# R2Cloud.net
KiCad netlist of a schematic drawn in Altium Designer
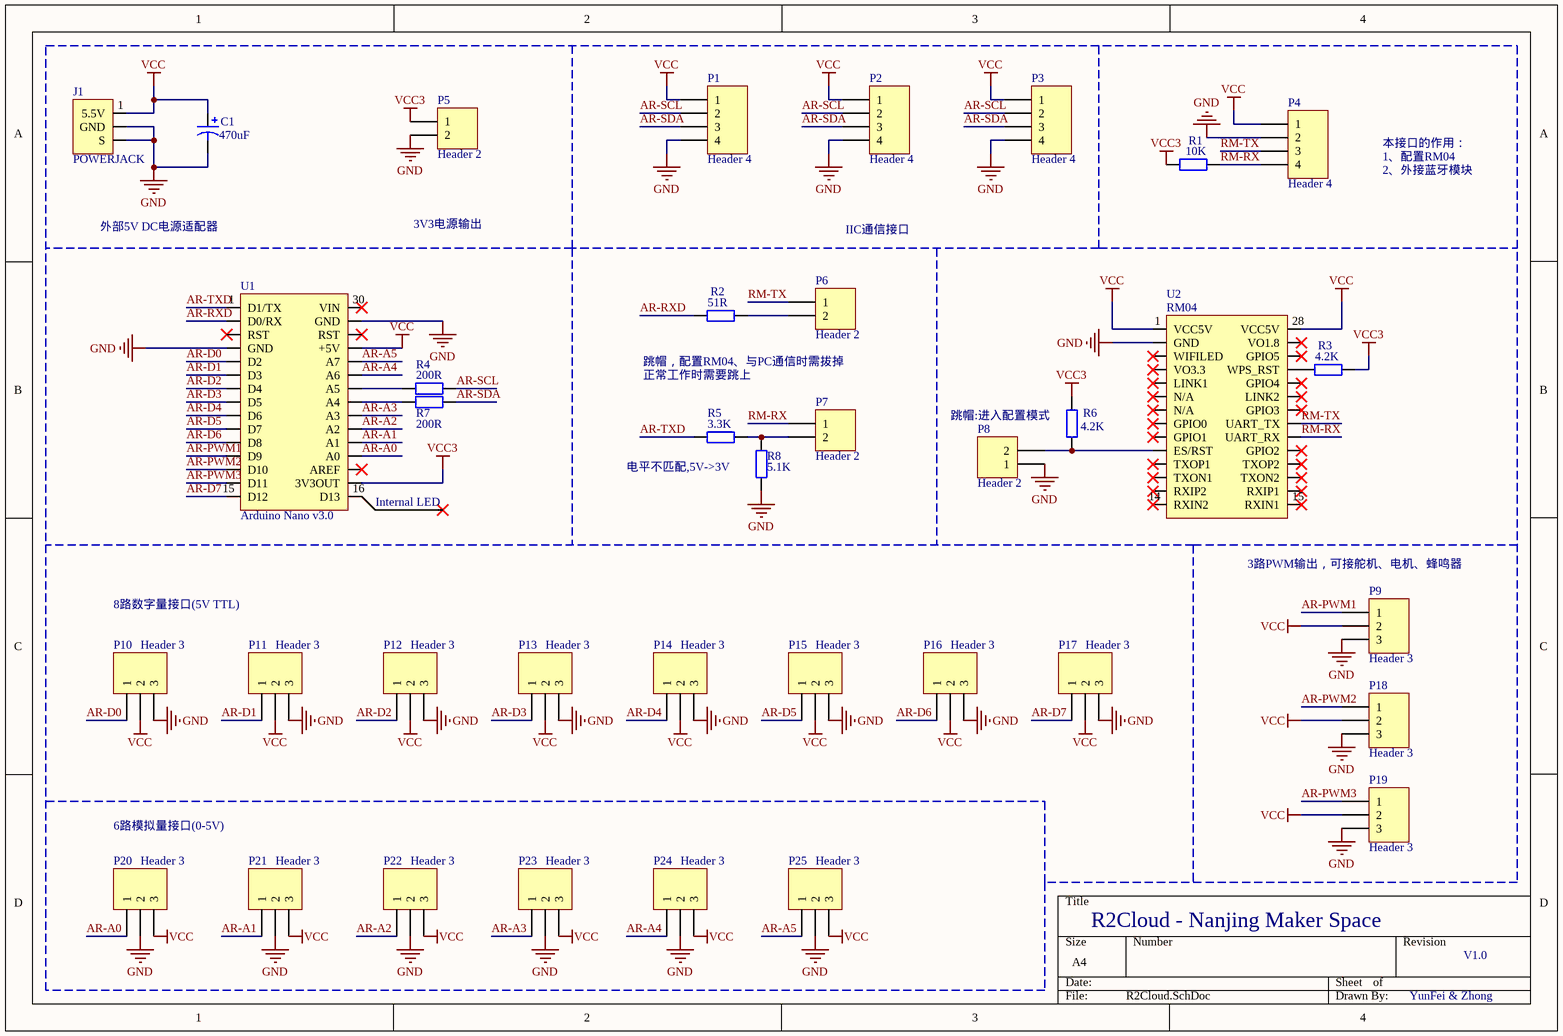
[diagram p0: R2Cloud.SchDoc]

(export (version "E")
  (design (tool "Eeschema 10.0.6"))
  (components
    (comp (ref "C1")
      (value "470uF")
      (footprint "C3.81/7.62")
      (description "Polarized Capacitor (Surface Mount)")
      (fields (field (name "Comment") "Cap Pol3") (field (name "PUBLISHER") "Altium Limited"))
      (libsource (lib "Miscellaneous Devices") (part "Cap Pol3"))
    )
    (comp (ref "J1") (value "POWERJACK") (footprint "POWERJACK") (libsource (lib "YAOJI") (part "POWERJACK")))
    (comp (ref "P1")
      (value "Header 4")
      (footprint "CON4-IIC")
      (description "Header, 4-Pin")
      (fields (field (name "PUBLISHER") "Altium Limited"))
      (libsource (lib "Miscellaneous Connectors") (part "Header 4"))
    )
    (comp (ref "P2")
      (value "Header 4")
      (footprint "CON4-IIC")
      (description "Header, 4-Pin")
      (fields (field (name "PUBLISHER") "Altium Limited"))
      (libsource (lib "Miscellaneous Connectors") (part "Header 4"))
    )
    (comp (ref "P3")
      (value "Header 4")
      (footprint "CON4-IIC")
      (description "Header, 4-Pin")
      (fields (field (name "PUBLISHER") "Altium Limited"))
      (libsource (lib "Miscellaneous Connectors") (part "Header 4"))
    )
    (comp (ref "P4")
      (value "Header 4")
      (footprint "CON4-EX")
      (description "Header, 4-Pin")
      (fields (field (name "PUBLISHER") "Altium Limited"))
      (libsource (lib "Miscellaneous Connectors") (part "Header 4"))
    )
    (comp (ref "P5")
      (value "Header 2")
      (footprint "CON2-V3.3")
      (description "Header, 2-Pin")
      (fields (field (name "PUBLISHER") "Altium Limited"))
      (libsource (lib "") (part "Header 2_1"))
    )
    (comp (ref "P6")
      (value "Header 2")
      (footprint "CON2-JUMPER")
      (description "Header, 2-Pin")
      (fields (field (name "PUBLISHER") "Altium Limited"))
      (libsource (lib "") (part "Header 2_1"))
    )
    (comp (ref "P7")
      (value "Header 2")
      (footprint "CON2-JUMPER")
      (description "Header, 2-Pin")
      (fields (field (name "PUBLISHER") "Altium Limited"))
      (libsource (lib "") (part "Header 2_1"))
    )
    (comp (ref "P8")
      (value "Header 2")
      (footprint "CON2-JUMPER")
      (description "Header, 2-Pin")
      (fields (field (name "PUBLISHER") "Altium Limited"))
      (libsource (lib "Miscellaneous Connectors") (part "Header 2"))
    )
    (comp (ref "P9")
      (value "Header 3")
      (footprint "CON3-PWM")
      (description "Header, 3-Pin")
      (fields (field (name "PUBLISHER") "Altium Limited"))
      (libsource (lib "") (part "Header 3_1"))
    )
    (comp (ref "P10")
      (value "Header 3")
      (footprint "CON3-D")
      (description "Header, 3-Pin")
      (fields (field (name "PUBLISHER") "Altium Limited"))
      (libsource (lib "Miscellaneous Connectors") (part "Header 3"))
    )
    (comp (ref "P11")
      (value "Header 3")
      (footprint "CON3-D")
      (description "Header, 3-Pin")
      (fields (field (name "PUBLISHER") "Altium Limited"))
      (libsource (lib "Miscellaneous Connectors") (part "Header 3"))
    )
    (comp (ref "P12")
      (value "Header 3")
      (footprint "CON3-D")
      (description "Header, 3-Pin")
      (fields (field (name "PUBLISHER") "Altium Limited"))
      (libsource (lib "Miscellaneous Connectors") (part "Header 3"))
    )
    (comp (ref "P13")
      (value "Header 3")
      (footprint "CON3-D")
      (description "Header, 3-Pin")
      (fields (field (name "PUBLISHER") "Altium Limited"))
      (libsource (lib "Miscellaneous Connectors") (part "Header 3"))
    )
    (comp (ref "P14")
      (value "Header 3")
      (footprint "CON3-D")
      (description "Header, 3-Pin")
      (fields (field (name "PUBLISHER") "Altium Limited"))
      (libsource (lib "Miscellaneous Connectors") (part "Header 3"))
    )
    (comp (ref "P15")
      (value "Header 3")
      (footprint "CON3-D")
      (description "Header, 3-Pin")
      (fields (field (name "PUBLISHER") "Altium Limited"))
      (libsource (lib "Miscellaneous Connectors") (part "Header 3"))
    )
    (comp (ref "P16")
      (value "Header 3")
      (footprint "CON3-D")
      (description "Header, 3-Pin")
      (fields (field (name "PUBLISHER") "Altium Limited"))
      (libsource (lib "Miscellaneous Connectors") (part "Header 3"))
    )
    (comp (ref "P17")
      (value "Header 3")
      (footprint "CON3-D")
      (description "Header, 3-Pin")
      (fields (field (name "PUBLISHER") "Altium Limited"))
      (libsource (lib "Miscellaneous Connectors") (part "Header 3"))
    )
    (comp (ref "P18")
      (value "Header 3")
      (footprint "CON3-PWM")
      (description "Header, 3-Pin")
      (fields (field (name "PUBLISHER") "Altium Limited"))
      (libsource (lib "") (part "Header 3_1"))
    )
    (comp (ref "P19")
      (value "Header 3")
      (footprint "CON3-PWM")
      (description "Header, 3-Pin")
      (fields (field (name "PUBLISHER") "Altium Limited"))
      (libsource (lib "") (part "Header 3_1"))
    )
    (comp (ref "P20")
      (value "Header 3")
      (footprint "CON3-A")
      (description "Header, 3-Pin")
      (fields (field (name "PUBLISHER") "Altium Limited"))
      (libsource (lib "Miscellaneous Connectors") (part "Header 3"))
    )
    (comp (ref "P21")
      (value "Header 3")
      (footprint "CON3-A")
      (description "Header, 3-Pin")
      (fields (field (name "PUBLISHER") "Altium Limited"))
      (libsource (lib "Miscellaneous Connectors") (part "Header 3"))
    )
    (comp (ref "P22")
      (value "Header 3")
      (footprint "CON3-A")
      (description "Header, 3-Pin")
      (fields (field (name "PUBLISHER") "Altium Limited"))
      (libsource (lib "Miscellaneous Connectors") (part "Header 3"))
    )
    (comp (ref "P23")
      (value "Header 3")
      (footprint "CON3-A")
      (description "Header, 3-Pin")
      (fields (field (name "PUBLISHER") "Altium Limited"))
      (libsource (lib "Miscellaneous Connectors") (part "Header 3"))
    )
    (comp (ref "P24")
      (value "Header 3")
      (footprint "CON3-A")
      (description "Header, 3-Pin")
      (fields (field (name "PUBLISHER") "Altium Limited"))
      (libsource (lib "Miscellaneous Connectors") (part "Header 3"))
    )
    (comp (ref "P25")
      (value "Header 3")
      (footprint "CON3-A")
      (description "Header, 3-Pin")
      (fields (field (name "PUBLISHER") "Altium Limited"))
      (libsource (lib "Miscellaneous Connectors") (part "Header 3"))
    )
    (comp (ref "R1")
      (value "10K")
      (footprint "0603")
      (description "Resistor")
      (fields (field (name "Comment") "Res2") (field (name "PUBLISHER") "Altium Limited"))
      (libsource (lib "Miscellaneous Devices") (part "Res2"))
    )
    (comp (ref "R2")
      (value "51R")
      (footprint "0603")
      (description "Resistor")
      (fields (field (name "Comment") "Res2") (field (name "PUBLISHER") "Altium Limited"))
      (libsource (lib "Miscellaneous Devices") (part "Res2"))
    )
    (comp (ref "R3")
      (value "4.2K")
      (footprint "0603")
      (description "Resistor")
      (fields (field (name "Comment") "Res2") (field (name "PUBLISHER") "Altium Limited"))
      (libsource (lib "Miscellaneous Devices") (part "Res2"))
    )
    (comp (ref "R4")
      (value "200R")
      (footprint "0603")
      (description "Resistor")
      (fields (field (name "Comment") "Res2") (field (name "PUBLISHER") "Altium Limited"))
      (libsource (lib "Miscellaneous Devices") (part "Res2"))
    )
    (comp (ref "R5")
      (value "3.3K")
      (footprint "0603")
      (description "Resistor")
      (fields (field (name "Comment") "Res2") (field (name "PUBLISHER") "Altium Limited"))
      (libsource (lib "Miscellaneous Devices") (part "Res2"))
    )
    (comp (ref "R6")
      (value "4.2K")
      (footprint "0603")
      (description "Resistor")
      (fields (field (name "Comment") "Res2") (field (name "PUBLISHER") "Altium Limited"))
      (libsource (lib "") (part "Res2_1"))
    )
    (comp (ref "R7")
      (value "200R")
      (footprint "0603")
      (description "Resistor")
      (fields (field (name "Comment") "Res2") (field (name "PUBLISHER") "Altium Limited"))
      (libsource (lib "Miscellaneous Devices") (part "Res2"))
    )
    (comp (ref "R8")
      (value "5.1K")
      (footprint "0603")
      (description "Resistor")
      (fields (field (name "Comment") "Res2") (field (name "PUBLISHER") "Altium Limited"))
      (libsource (lib "") (part "Res2_2"))
    )
    (comp (ref "U1")
      (value "Arduino Nano v3.0")
      (footprint "Arduino Nano v3.0")
      (libsource (lib "YAOJI") (part "Arduino Nano v3.0"))
    )
    (comp (ref "U2") (value "RM04") (footprint "RM-04") (libsource (lib "YAOJI") (part "RM04")))
  )
  (nets
    (net (code "1") (name "/AR-A0") (class "Default")
      (node (ref "P20") (pin "1") (pinfunction "1_1") (pintype "passive"))
      (node (ref "U1") (pin "19") (pinfunction "A0_19") (pintype "passive"))
    )
    (net (code "2") (name "/AR-A1") (class "Default")
      (node (ref "P21") (pin "1") (pinfunction "1_1") (pintype "passive"))
      (node (ref "U1") (pin "20") (pinfunction "A1_20") (pintype "passive"))
    )
    (net (code "3") (name "/AR-A2") (class "Default")
      (node (ref "P22") (pin "1") (pinfunction "1_1") (pintype "passive"))
      (node (ref "U1") (pin "21") (pinfunction "A2_21") (pintype "passive"))
    )
    (net (code "4") (name "/AR-A3") (class "Default")
      (node (ref "P23") (pin "1") (pinfunction "1_1") (pintype "passive"))
      (node (ref "U1") (pin "22") (pinfunction "A3_22") (pintype "passive"))
    )
    (net (code "5") (name "/AR-A4") (class "Default")
      (node (ref "P24") (pin "1") (pinfunction "1_1") (pintype "passive"))
      (node (ref "U1") (pin "25") (pinfunction "A6_25") (pintype "passive"))
    )
    (net (code "6") (name "/AR-A5") (class "Default")
      (node (ref "P25") (pin "1") (pinfunction "1_1") (pintype "passive"))
      (node (ref "U1") (pin "26") (pinfunction "A7_26") (pintype "passive"))
    )
    (net (code "7") (name "/AR-D0") (class "Default")
      (node (ref "P10") (pin "1") (pinfunction "1_1") (pintype "passive"))
      (node (ref "U1") (pin "5") (pinfunction "D2_5") (pintype "passive"))
    )
    (net (code "8") (name "/AR-D1") (class "Default")
      (node (ref "P11") (pin "1") (pinfunction "1_1") (pintype "passive"))
      (node (ref "U1") (pin "6") (pinfunction "D3_6") (pintype "passive"))
    )
    (net (code "9") (name "/AR-D2") (class "Default")
      (node (ref "P12") (pin "1") (pinfunction "1_1") (pintype "passive"))
      (node (ref "U1") (pin "7") (pinfunction "D4_7") (pintype "passive"))
    )
    (net (code "10") (name "/AR-D3") (class "Default")
      (node (ref "P13") (pin "1") (pinfunction "1_1") (pintype "passive"))
      (node (ref "U1") (pin "8") (pinfunction "D5_8") (pintype "passive"))
    )
    (net (code "11") (name "/AR-D4") (class "Default")
      (node (ref "P14") (pin "1") (pinfunction "1_1") (pintype "passive"))
      (node (ref "U1") (pin "9") (pinfunction "D6_9") (pintype "passive"))
    )
    (net (code "12") (name "/AR-D5") (class "Default")
      (node (ref "P15") (pin "1") (pinfunction "1_1") (pintype "passive"))
      (node (ref "U1") (pin "10") (pinfunction "D7_10") (pintype "passive"))
    )
    (net (code "13") (name "/AR-D6") (class "Default")
      (node (ref "P16") (pin "1") (pinfunction "1_1") (pintype "passive"))
      (node (ref "U1") (pin "11") (pinfunction "D8_11") (pintype "passive"))
    )
    (net (code "14") (name "/AR-D7") (class "Default")
      (node (ref "P17") (pin "1") (pinfunction "1_1") (pintype "passive"))
      (node (ref "U1") (pin "15") (pinfunction "D12_15") (pintype "passive"))
    )
    (net (code "15") (name "/AR-PWM1") (class "Default")
      (node (ref "P9") (pin "1") (pinfunction "1_1") (pintype "passive"))
      (node (ref "U1") (pin "12") (pinfunction "D9_12") (pintype "passive"))
    )
    (net (code "16") (name "/AR-PWM2") (class "Default")
      (node (ref "P18") (pin "1") (pinfunction "1_1") (pintype "passive"))
      (node (ref "U1") (pin "13") (pinfunction "D10_13") (pintype "passive"))
    )
    (net (code "17") (name "/AR-PWM3") (class "Default")
      (node (ref "P19") (pin "1") (pinfunction "1_1") (pintype "passive"))
      (node (ref "U1") (pin "14") (pinfunction "D11_14") (pintype "passive"))
    )
    (net (code "18") (name "/AR-RXD") (class "Default")
      (node (ref "R2") (pin "2") (pinfunction "2_2") (pintype "passive"))
      (node (ref "U1") (pin "2") (pinfunction "D0/RX_2") (pintype "passive"))
    )
    (net (code "19") (name "/AR-SCL") (class "Default")
      (node (ref "P1") (pin "2") (pinfunction "2_2") (pintype "passive"))
      (node (ref "P2") (pin "2") (pinfunction "2_2") (pintype "passive"))
      (node (ref "P3") (pin "2") (pinfunction "2_2") (pintype "passive"))
      (node (ref "R4") (pin "1") (pinfunction "1_1") (pintype "passive"))
    )
    (net (code "20") (name "/AR-SDA") (class "Default")
      (node (ref "P1") (pin "3") (pinfunction "3_3") (pintype "passive"))
      (node (ref "P2") (pin "3") (pinfunction "3_3") (pintype "passive"))
      (node (ref "P3") (pin "3") (pinfunction "3_3") (pintype "passive"))
      (node (ref "R7") (pin "1") (pinfunction "1_1") (pintype "passive"))
    )
    (net (code "21") (name "/AR-TXD") (class "Default")
      (node (ref "R5") (pin "2") (pinfunction "2_2") (pintype "passive"))
      (node (ref "U1") (pin "1") (pinfunction "D1/TX_1") (pintype "passive"))
    )
    (net (code "22") (name "/RM-RX") (class "Default")
      (node (ref "P4") (pin "4") (pinfunction "4_4") (pintype "passive"))
      (node (ref "P7") (pin "1") (pinfunction "1_1") (pintype "passive"))
      (node (ref "R1") (pin "1") (pinfunction "1_1") (pintype "passive"))
      (node (ref "U2") (pin "20") (pinfunction "UART_RX_20") (pintype "passive"))
    )
    (net (code "23") (name "/RM-TX") (class "Default")
      (node (ref "P4") (pin "3") (pinfunction "3_3") (pintype "passive"))
      (node (ref "P6") (pin "1") (pinfunction "1_1") (pintype "passive"))
      (node (ref "U2") (pin "21") (pinfunction "UART_TX_21") (pintype "passive"))
    )
    (net (code "24") (name "GND") (class "Default")
      (node (ref "C1") (pin "2") (pinfunction "2_2") (pintype "passive"))
      (node (ref "J1") (pin "2") (pinfunction "GND_2") (pintype "passive"))
      (node (ref "J1") (pin "3") (pinfunction "S_3") (pintype "passive"))
      (node (ref "P1") (pin "4") (pinfunction "4_4") (pintype "passive"))
      (node (ref "P10") (pin "3") (pinfunction "3_3") (pintype "passive"))
      (node (ref "P11") (pin "3") (pinfunction "3_3") (pintype "passive"))
      (node (ref "P12") (pin "3") (pinfunction "3_3") (pintype "passive"))
      (node (ref "P13") (pin "3") (pinfunction "3_3") (pintype "passive"))
      (node (ref "P14") (pin "3") (pinfunction "3_3") (pintype "passive"))
      (node (ref "P15") (pin "3") (pinfunction "3_3") (pintype "passive"))
      (node (ref "P16") (pin "3") (pinfunction "3_3") (pintype "passive"))
      (node (ref "P17") (pin "3") (pinfunction "3_3") (pintype "passive"))
      (node (ref "P18") (pin "3") (pinfunction "3_3") (pintype "passive"))
      (node (ref "P19") (pin "3") (pinfunction "3_3") (pintype "passive"))
      (node (ref "P2") (pin "4") (pinfunction "4_4") (pintype "passive"))
      (node (ref "P20") (pin "2") (pinfunction "2_2") (pintype "passive"))
      (node (ref "P21") (pin "2") (pinfunction "2_2") (pintype "passive"))
      (node (ref "P22") (pin "2") (pinfunction "2_2") (pintype "passive"))
      (node (ref "P23") (pin "2") (pinfunction "2_2") (pintype "passive"))
      (node (ref "P24") (pin "2") (pinfunction "2_2") (pintype "passive"))
      (node (ref "P25") (pin "2") (pinfunction "2_2") (pintype "passive"))
      (node (ref "P3") (pin "4") (pinfunction "4_4") (pintype "passive"))
      (node (ref "P4") (pin "2") (pinfunction "2_2") (pintype "passive"))
      (node (ref "P5") (pin "2") (pinfunction "2_2") (pintype "passive"))
      (node (ref "P8") (pin "1") (pinfunction "1_1") (pintype "passive"))
      (node (ref "P9") (pin "3") (pinfunction "3_3") (pintype "passive"))
      (node (ref "R8") (pin "2") (pinfunction "2_2") (pintype "passive"))
      (node (ref "U1") (pin "29") (pinfunction "GND_29") (pintype "passive"))
      (node (ref "U1") (pin "4") (pinfunction "GND_4") (pintype "passive"))
      (node (ref "U2") (pin "2") (pinfunction "GND_2") (pintype "passive"))
    )
    (net (code "25") (name "Net-(P6-Pad2)") (class "Default")
      (node (ref "P6") (pin "2") (pinfunction "2_2") (pintype "passive"))
      (node (ref "R2") (pin "1") (pinfunction "1_1") (pintype "passive"))
    )
    (net (code "26") (name "Net-(P7-Pad2)") (class "Default")
      (node (ref "P7") (pin "2") (pinfunction "2_2") (pintype "passive"))
      (node (ref "R5") (pin "1") (pinfunction "1_1") (pintype "passive"))
      (node (ref "R8") (pin "1") (pinfunction "1_1") (pintype "passive"))
    )
    (net (code "27") (name "Net-(U1-A4)") (class "Default")
      (node (ref "R7") (pin "2") (pinfunction "2_2") (pintype "passive"))
      (node (ref "U1") (pin "23") (pinfunction "A4_23") (pintype "passive"))
    )
    (net (code "28") (name "Net-(U1-A5)") (class "Default")
      (node (ref "R4") (pin "2") (pinfunction "2_2") (pintype "passive"))
      (node (ref "U1") (pin "24") (pinfunction "A5_24") (pintype "passive"))
    )
    (net (code "29") (name "Net-(U2-ES{slash}RST)") (class "Default")
      (node (ref "P8") (pin "2") (pinfunction "2_2") (pintype "passive"))
      (node (ref "R6") (pin "1") (pinfunction "1_1") (pintype "passive"))
      (node (ref "U2") (pin "10") (pinfunction "ES/RST_10") (pintype "passive"))
    )
    (net (code "30") (name "Net-(U2-WPS_RST)") (class "Default")
      (node (ref "R3") (pin "2") (pinfunction "2_2") (pintype "passive"))
      (node (ref "U2") (pin "25") (pinfunction "WPS_RST_25") (pintype "passive"))
    )
    (net (code "31") (name "VCC") (class "Default")
      (node (ref "C1") (pin "1") (pinfunction "1_1") (pintype "passive"))
      (node (ref "J1") (pin "1") (pinfunction "5.5V_1") (pintype "passive"))
      (node (ref "P1") (pin "1") (pinfunction "1_1") (pintype "passive"))
      (node (ref "P10") (pin "2") (pinfunction "2_2") (pintype "passive"))
      (node (ref "P11") (pin "2") (pinfunction "2_2") (pintype "passive"))
      (node (ref "P12") (pin "2") (pinfunction "2_2") (pintype "passive"))
      (node (ref "P13") (pin "2") (pinfunction "2_2") (pintype "passive"))
      (node (ref "P14") (pin "2") (pinfunction "2_2") (pintype "passive"))
      (node (ref "P15") (pin "2") (pinfunction "2_2") (pintype "passive"))
      (node (ref "P16") (pin "2") (pinfunction "2_2") (pintype "passive"))
      (node (ref "P17") (pin "2") (pinfunction "2_2") (pintype "passive"))
      (node (ref "P18") (pin "2") (pinfunction "2_2") (pintype "passive"))
      (node (ref "P19") (pin "2") (pinfunction "2_2") (pintype "passive"))
      (node (ref "P2") (pin "1") (pinfunction "1_1") (pintype "passive"))
      (node (ref "P20") (pin "3") (pinfunction "3_3") (pintype "passive"))
      (node (ref "P21") (pin "3") (pinfunction "3_3") (pintype "passive"))
      (node (ref "P22") (pin "3") (pinfunction "3_3") (pintype "passive"))
      (node (ref "P23") (pin "3") (pinfunction "3_3") (pintype "passive"))
      (node (ref "P24") (pin "3") (pinfunction "3_3") (pintype "passive"))
      (node (ref "P25") (pin "3") (pinfunction "3_3") (pintype "passive"))
      (node (ref "P3") (pin "1") (pinfunction "1_1") (pintype "passive"))
      (node (ref "P4") (pin "1") (pinfunction "1_1") (pintype "passive"))
      (node (ref "P9") (pin "2") (pinfunction "2_2") (pintype "passive"))
      (node (ref "U1") (pin "27") (pinfunction "+5V_27") (pintype "passive"))
      (node (ref "U2") (pin "1") (pinfunction "VCC5V_1") (pintype "passive"))
      (node (ref "U2") (pin "28") (pinfunction "VCC5V_28") (pintype "passive"))
    )
    (net (code "32") (name "VCC3") (class "Default")
      (node (ref "P5") (pin "1") (pinfunction "1_1") (pintype "passive"))
      (node (ref "R1") (pin "2") (pinfunction "2_2") (pintype "passive"))
      (node (ref "R3") (pin "1") (pinfunction "1_1") (pintype "passive"))
      (node (ref "R6") (pin "2") (pinfunction "2_2") (pintype "passive"))
      (node (ref "U1") (pin "17") (pinfunction "3V3OUT_17") (pintype "passive"))
    )
    (net (code "33") (name "unconnected-(U1-AREF-Pad18)") (class "Default")
      (node (ref "U1") (pin "18") (pinfunction "AREF_18") (pintype "passive+no_connect"))
    )
    (net (code "34") (name "unconnected-(U1-D13-Pad16)") (class "Default")
      (node (ref "U1") (pin "16") (pinfunction "D13_16") (pintype "passive"))
    )
    (net (code "35") (name "unconnected-(U1-RST-Pad3)") (class "Default")
      (node (ref "U1") (pin "3") (pinfunction "RST_3") (pintype "passive+no_connect"))
    )
    (net (code "36") (name "unconnected-(U1-RST-Pad28)") (class "Default")
      (node (ref "U1") (pin "28") (pinfunction "RST_28") (pintype "passive+no_connect"))
    )
    (net (code "37") (name "unconnected-(U1-VIN-Pad30)") (class "Default")
      (node (ref "U1") (pin "30") (pinfunction "VIN_30") (pintype "passive+no_connect"))
    )
    (net (code "38") (name "unconnected-(U2-GPIO0-Pad8)") (class "Default")
      (node (ref "U2") (pin "8") (pinfunction "GPIO0_8") (pintype "passive+no_connect"))
    )
    (net (code "39") (name "unconnected-(U2-GPIO1-Pad9)") (class "Default")
      (node (ref "U2") (pin "9") (pinfunction "GPIO1_9") (pintype "passive+no_connect"))
    )
    (net (code "40") (name "unconnected-(U2-GPIO2-Pad19)") (class "Default")
      (node (ref "U2") (pin "19") (pinfunction "GPIO2_19") (pintype "passive+no_connect"))
    )
    (net (code "41") (name "unconnected-(U2-GPIO3-Pad22)") (class "Default")
      (node (ref "U2") (pin "22") (pinfunction "GPIO3_22") (pintype "passive+no_connect"))
    )
    (net (code "42") (name "unconnected-(U2-GPIO4-Pad24)") (class "Default")
      (node (ref "U2") (pin "24") (pinfunction "GPIO4_24") (pintype "passive+no_connect"))
    )
    (net (code "43") (name "unconnected-(U2-GPIO5-Pad26)") (class "Default")
      (node (ref "U2") (pin "26") (pinfunction "GPIO5_26") (pintype "passive+no_connect"))
    )
    (net (code "44") (name "unconnected-(U2-LINK1-Pad5)") (class "Default")
      (node (ref "U2") (pin "5") (pinfunction "LINK1_5") (pintype "passive+no_connect"))
    )
    (net (code "45") (name "unconnected-(U2-LINK2-Pad23)") (class "Default")
      (node (ref "U2") (pin "23") (pinfunction "LINK2_23") (pintype "passive+no_connect"))
    )
    (net (code "46") (name "unconnected-(U2-N{slash}A-Pad6)") (class "Default")
      (node (ref "U2") (pin "6") (pinfunction "N/A_6") (pintype "passive+no_connect"))
    )
    (net (code "47") (name "unconnected-(U2-N{slash}A-Pad7)") (class "Default")
      (node (ref "U2") (pin "7") (pinfunction "N/A_7") (pintype "passive+no_connect"))
    )
    (net (code "48") (name "unconnected-(U2-RXIN1-Pad15)") (class "Default")
      (node (ref "U2") (pin "15") (pinfunction "RXIN1_15") (pintype "passive+no_connect"))
    )
    (net (code "49") (name "unconnected-(U2-RXIN2-Pad14)") (class "Default")
      (node (ref "U2") (pin "14") (pinfunction "RXIN2_14") (pintype "passive+no_connect"))
    )
    (net (code "50") (name "unconnected-(U2-RXIP1-Pad16)") (class "Default")
      (node (ref "U2") (pin "16") (pinfunction "RXIP1_16") (pintype "passive+no_connect"))
    )
    (net (code "51") (name "unconnected-(U2-RXIP2-Pad13)") (class "Default")
      (node (ref "U2") (pin "13") (pinfunction "RXIP2_13") (pintype "passive+no_connect"))
    )
    (net (code "52") (name "unconnected-(U2-TXON1-Pad12)") (class "Default")
      (node (ref "U2") (pin "12") (pinfunction "TXON1_12") (pintype "passive+no_connect"))
    )
    (net (code "53") (name "unconnected-(U2-TXON2-Pad17)") (class "Default")
      (node (ref "U2") (pin "17") (pinfunction "TXON2_17") (pintype "passive+no_connect"))
    )
    (net (code "54") (name "unconnected-(U2-TXOP1-Pad11)") (class "Default")
      (node (ref "U2") (pin "11") (pinfunction "TXOP1_11") (pintype "passive+no_connect"))
    )
    (net (code "55") (name "unconnected-(U2-TXOP2-Pad18)") (class "Default")
      (node (ref "U2") (pin "18") (pinfunction "TXOP2_18") (pintype "passive+no_connect"))
    )
    (net (code "56") (name "unconnected-(U2-VO1.8-Pad27)") (class "Default")
      (node (ref "U2") (pin "27") (pinfunction "VO1.8_27") (pintype "passive+no_connect"))
    )
    (net (code "57") (name "unconnected-(U2-VO3.3-Pad4)") (class "Default")
      (node (ref "U2") (pin "4") (pinfunction "VO3.3_4") (pintype "passive+no_connect"))
    )
    (net (code "58") (name "unconnected-(U2-WIFILED-Pad3)") (class "Default")
      (node (ref "U2") (pin "3") (pinfunction "WIFILED_3") (pintype "passive+no_connect"))
    )
  )
)
